# DPPXHK_POWER_SOURCE.net
KiCad netlist of a schematic drawn in Altium Designer
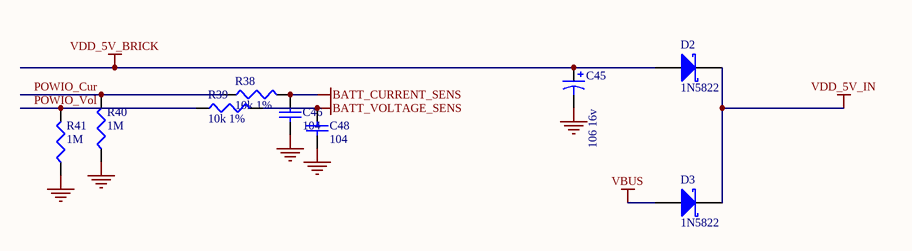
[diagram p0: DPPXHK_POWER_SOURCE.SCHDOC]

(export (version "E")
  (design (tool "Eeschema 10.0.6"))
  (components
    (comp (ref "C45")
      (value "106 16v")
      (footprint "LC0402")
      (description "Polarized Capacitor (Surface Mount)")
      (fields (field (name "PUBLISHER") "Altium Limited"))
      (libsource (lib "Miscellaneous Devices") (part "Cap Pol3"))
    )
    (comp (ref "C46")
      (value "104")
      (footprint "LC0402")
      (description "Capacitor")
      (fields (field (name "PUBLISHER") "Altium Limited"))
      (libsource (lib "Miscellaneous Devices") (part "Cap"))
    )
    (comp (ref "C48")
      (value "104")
      (footprint "LC0402")
      (description "Capacitor")
      (fields (field (name "PUBLISHER") "Altium Limited"))
      (libsource (lib "Miscellaneous Devices") (part "Cap"))
    )
    (comp (ref "D2")
      (value "1N5822")
      (footprint "SMA")
      (description "Schottky Diode")
      (fields (field (name "PUBLISHER") "Altium Limited"))
      (libsource (lib "Miscellaneous Devices") (part "D Schottky"))
    )
    (comp (ref "D3")
      (value "1N5822")
      (footprint "SMA")
      (description "Schottky Diode")
      (fields (field (name "PUBLISHER") "Altium Limited"))
      (libsource (lib "Miscellaneous Devices") (part "D Schottky"))
    )
    (comp (ref "R38")
      (value "10k 1%")
      (footprint "0402R")
      (description "Resistor")
      (fields (field (name "PUBLISHER") "Altium Limited"))
      (libsource (lib "Miscellaneous Devices") (part "Res3"))
    )
    (comp (ref "R39")
      (value "10k 1%")
      (footprint "0402R")
      (description "Resistor")
      (fields (field (name "PUBLISHER") "Altium Limited"))
      (libsource (lib "Miscellaneous Devices") (part "Res3"))
    )
    (comp (ref "R40")
      (value "1M")
      (footprint "0402R")
      (description "Resistor")
      (fields (field (name "PUBLISHER") "Altium Limited"))
      (libsource (lib "Miscellaneous Devices") (part "Res3"))
    )
    (comp (ref "R41")
      (value "1M")
      (footprint "0402R")
      (description "Resistor")
      (fields (field (name "PUBLISHER") "Altium Limited"))
      (libsource (lib "Miscellaneous Devices") (part "Res3"))
    )
  )
  (nets
    (net (code "1") (name "/POWIO_Cur") (class "Default")
      (node (ref "R38") (pin "1") (pinfunction "1_1") (pintype "passive"))
      (node (ref "R40") (pin "2") (pinfunction "2_2") (pintype "passive"))
    )
    (net (code "2") (name "/POWIO_Vol") (class "Default")
      (node (ref "R39") (pin "1") (pinfunction "1_1") (pintype "passive"))
      (node (ref "R41") (pin "2") (pinfunction "2_2") (pintype "passive"))
    )
    (net (code "3") (name "BATT_CURRENT_SENS") (class "Default")
      (node (ref "C46") (pin "2") (pinfunction "2_2") (pintype "passive"))
      (node (ref "R38") (pin "2") (pinfunction "2_2") (pintype "passive"))
    )
    (net (code "4") (name "BATT_VOLTAGE_SENS") (class "Default")
      (node (ref "C48") (pin "2") (pinfunction "2_2") (pintype "passive"))
      (node (ref "R39") (pin "2") (pinfunction "2_2") (pintype "passive"))
    )
    (net (code "5") (name "GND") (class "Default")
      (node (ref "C45") (pin "2") (pinfunction "2_2") (pintype "passive"))
      (node (ref "C46") (pin "1") (pinfunction "1_1") (pintype "passive"))
      (node (ref "C48") (pin "1") (pinfunction "1_1") (pintype "passive"))
      (node (ref "R40") (pin "1") (pinfunction "1_1") (pintype "passive"))
      (node (ref "R41") (pin "1") (pinfunction "1_1") (pintype "passive"))
    )
    (net (code "6") (name "VBUS") (class "Default")
      (node (ref "D3") (pin "1") (pinfunction "A_1") (pintype "passive"))
    )
    (net (code "7") (name "VDD_5V_BRICK") (class "Default")
      (node (ref "C45") (pin "1") (pinfunction "1_1") (pintype "passive"))
      (node (ref "D2") (pin "1") (pinfunction "A_1") (pintype "passive"))
    )
    (net (code "8") (name "VDD_5V_IN") (class "Default")
      (node (ref "D2") (pin "2") (pinfunction "K_2") (pintype "passive"))
      (node (ref "D3") (pin "2") (pinfunction "K_2") (pintype "passive"))
    )
  )
)
